# bpf-UHF-SAW-SF2446E.net
KiCad netlist of a schematic drawn in EAGLE
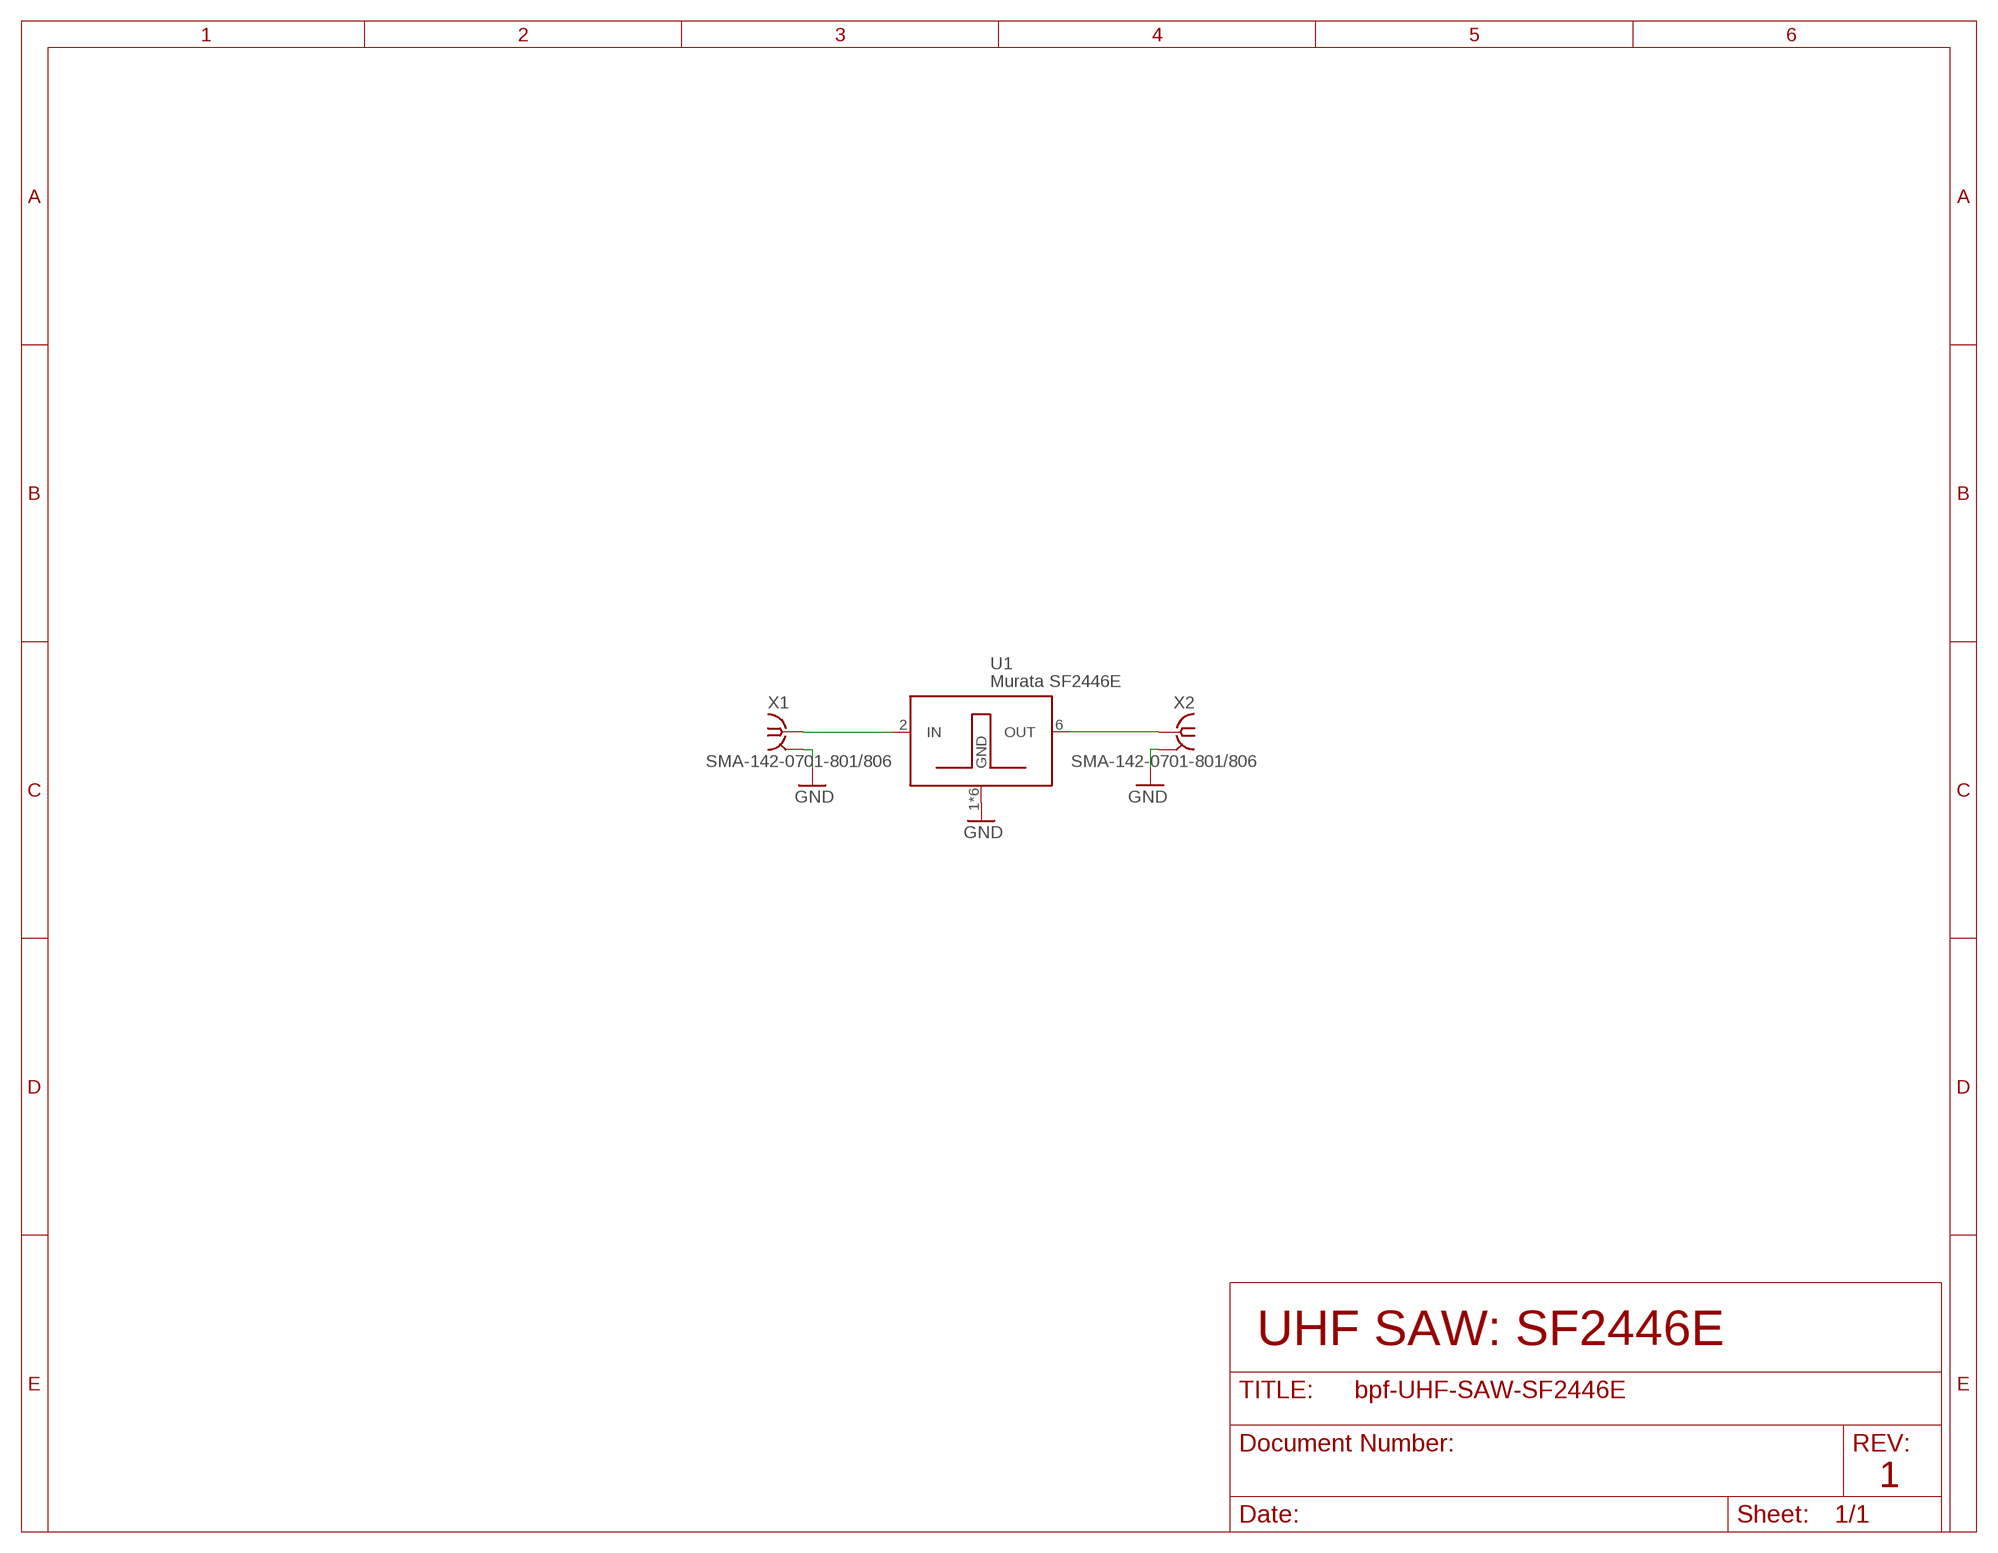
[diagram p0: schematic, sheet 1]

(export (version "E")
  (design (tool "Eeschema 10.0.6"))
  (components
    (comp (ref "U1")
      (value "Murata SF2446E")
      (footprint "eagle-import:3.8X3.8")
      (libsource (lib "eagle-import") (part "856930"))
    )
    (comp (ref "X1")
      (value "SMA-142-0701-801/806")
      (footprint "eagle-import:J502-ND-142-0701-801_806")
      (fields (field (name "MF") "JOHNSON COMPONENTS") (field (name "MPN") "142-0701-801"))
      (libsource (lib "eagle-import") (part "SMA-142-0701-801/806"))
    )
    (comp (ref "X2")
      (value "SMA-142-0701-801/806")
      (footprint "eagle-import:J502-ND-142-0701-801_806")
      (fields (field (name "MF") "JOHNSON COMPONENTS") (field (name "MPN") "142-0701-801"))
      (libsource (lib "eagle-import") (part "SMA-142-0701-801/806"))
    )
  )
  (nets
    (net (code "1") (name "GND") (class "Default")
      (node (ref "U1") (pin "1") (pinfunction "GND_1") (pintype "power_in"))
      (node (ref "U1") (pin "3") (pinfunction "GND_3") (pintype "power_in"))
      (node (ref "U1") (pin "4") (pinfunction "GND_4") (pintype "power_in"))
      (node (ref "U1") (pin "5") (pinfunction "GND_5") (pintype "power_in"))
      (node (ref "U1") (pin "7") (pinfunction "GND_7") (pintype "power_in"))
      (node (ref "U1") (pin "8") (pinfunction "GND_8") (pintype "power_in"))
      (node (ref "X1") (pin "G@1") (pinfunction "2_G@1") (pintype "passive"))
      (node (ref "X1") (pin "G@2") (pinfunction "2_G@2") (pintype "passive"))
      (node (ref "X1") (pin "G@3") (pinfunction "2_G@3") (pintype "passive"))
      (node (ref "X1") (pin "G@4") (pinfunction "2_G@4") (pintype "passive"))
      (node (ref "X2") (pin "G@1") (pinfunction "2_G@1") (pintype "passive"))
      (node (ref "X2") (pin "G@2") (pinfunction "2_G@2") (pintype "passive"))
      (node (ref "X2") (pin "G@3") (pinfunction "2_G@3") (pintype "passive"))
      (node (ref "X2") (pin "G@4") (pinfunction "2_G@4") (pintype "passive"))
    )
    (net (code "2") (name "Net-(U1-IN)") (class "Default")
      (node (ref "U1") (pin "2") (pinfunction "IN_2") (pintype "input"))
      (node (ref "X1") (pin "1") (pinfunction "1_1") (pintype "passive"))
    )
    (net (code "3") (name "Net-(U1-OUT)") (class "Default")
      (node (ref "U1") (pin "6") (pinfunction "OUT_6") (pintype "output"))
      (node (ref "X2") (pin "1") (pinfunction "1_1") (pintype "passive"))
    )
  )
)
